# key_pad.net
KiCad netlist of a schematic drawn in Altium Designer
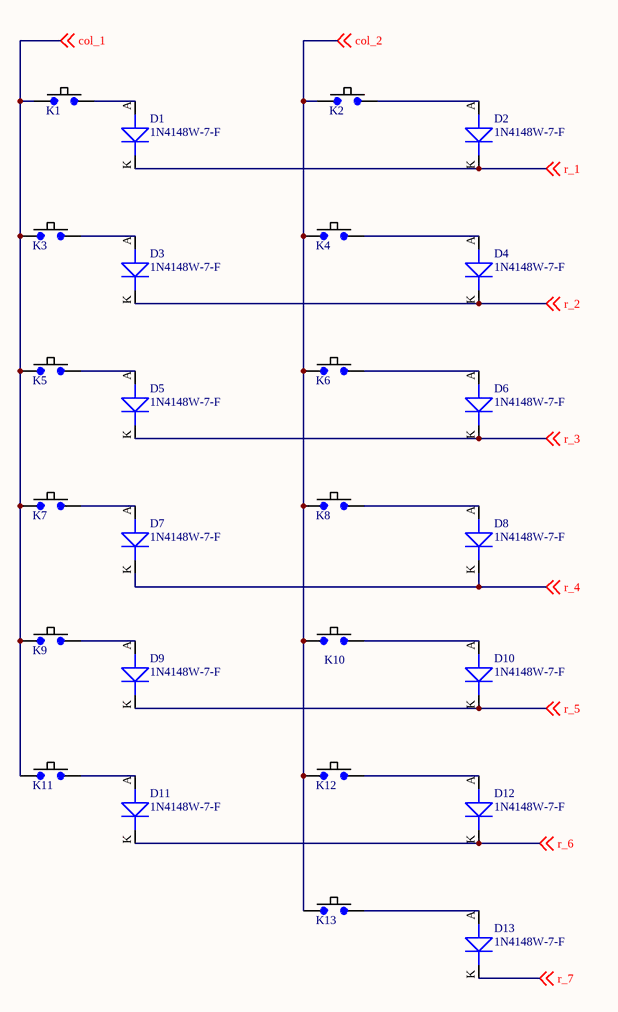
[diagram p0: key_pad.SchDoc]

(export (version "E")
  (design (tool "Eeschema 10.0.6"))
  (components
    (comp (ref "D1")
      (value "1N4148W-7-F")
      (footprint "DIO_SOD-123")
      (description "Diode Standard 100V 300mA (DC) Surface Mount SOD-123")
      (fields (field (name "MANUFACTURER") "FAIRCHILD"))
      (libsource (lib "ESTEEMPCBLIB") (part "DIO_100V-300mA-SOD123"))
    )
    (comp (ref "D2")
      (value "1N4148W-7-F")
      (footprint "DIO_SOD-123")
      (description "Diode Standard 100V 300mA (DC) Surface Mount SOD-123")
      (fields (field (name "MANUFACTURER") "FAIRCHILD"))
      (libsource (lib "ESTEEMPCBLIB") (part "DIO_100V-300mA-SOD123"))
    )
    (comp (ref "D3")
      (value "1N4148W-7-F")
      (footprint "DIO_SOD-123")
      (description "Diode Standard 100V 300mA (DC) Surface Mount SOD-123")
      (fields (field (name "MANUFACTURER") "FAIRCHILD"))
      (libsource (lib "ESTEEMPCBLIB") (part "DIO_100V-300mA-SOD123"))
    )
    (comp (ref "D4")
      (value "1N4148W-7-F")
      (footprint "DIO_SOD-123")
      (description "Diode Standard 100V 300mA (DC) Surface Mount SOD-123")
      (fields (field (name "MANUFACTURER") "FAIRCHILD"))
      (libsource (lib "ESTEEMPCBLIB") (part "DIO_100V-300mA-SOD123"))
    )
    (comp (ref "D5")
      (value "1N4148W-7-F")
      (footprint "DIO_SOD-123")
      (description "Diode Standard 100V 300mA (DC) Surface Mount SOD-123")
      (fields (field (name "MANUFACTURER") "FAIRCHILD"))
      (libsource (lib "ESTEEMPCBLIB") (part "DIO_100V-300mA-SOD123"))
    )
    (comp (ref "D6")
      (value "1N4148W-7-F")
      (footprint "DIO_SOD-123")
      (description "Diode Standard 100V 300mA (DC) Surface Mount SOD-123")
      (fields (field (name "MANUFACTURER") "FAIRCHILD"))
      (libsource (lib "ESTEEMPCBLIB") (part "DIO_100V-300mA-SOD123"))
    )
    (comp (ref "D7")
      (value "1N4148W-7-F")
      (footprint "DIO_SOD-123")
      (description "Diode Standard 100V 300mA (DC) Surface Mount SOD-123")
      (fields (field (name "MANUFACTURER") "FAIRCHILD"))
      (libsource (lib "ESTEEMPCBLIB") (part "DIO_100V-300mA-SOD123"))
    )
    (comp (ref "D8")
      (value "1N4148W-7-F")
      (footprint "DIO_SOD-123")
      (description "Diode Standard 100V 300mA (DC) Surface Mount SOD-123")
      (fields (field (name "MANUFACTURER") "FAIRCHILD"))
      (libsource (lib "ESTEEMPCBLIB") (part "DIO_100V-300mA-SOD123"))
    )
    (comp (ref "D9")
      (value "1N4148W-7-F")
      (footprint "DIO_SOD-123")
      (description "Diode Standard 100V 300mA (DC) Surface Mount SOD-123")
      (fields (field (name "MANUFACTURER") "FAIRCHILD"))
      (libsource (lib "ESTEEMPCBLIB") (part "DIO_100V-300mA-SOD123"))
    )
    (comp (ref "D10")
      (value "1N4148W-7-F")
      (footprint "DIO_SOD-123")
      (description "Diode Standard 100V 300mA (DC) Surface Mount SOD-123")
      (fields (field (name "MANUFACTURER") "FAIRCHILD"))
      (libsource (lib "ESTEEMPCBLIB") (part "DIO_100V-300mA-SOD123"))
    )
    (comp (ref "D11")
      (value "1N4148W-7-F")
      (footprint "DIO_SOD-123")
      (description "Diode Standard 100V 300mA (DC) Surface Mount SOD-123")
      (fields (field (name "MANUFACTURER") "FAIRCHILD"))
      (libsource (lib "ESTEEMPCBLIB") (part "DIO_100V-300mA-SOD123"))
    )
    (comp (ref "D12")
      (value "1N4148W-7-F")
      (footprint "DIO_SOD-123")
      (description "Diode Standard 100V 300mA (DC) Surface Mount SOD-123")
      (fields (field (name "MANUFACTURER") "FAIRCHILD"))
      (libsource (lib "ESTEEMPCBLIB") (part "DIO_100V-300mA-SOD123"))
    )
    (comp (ref "D13")
      (value "1N4148W-7-F")
      (footprint "DIO_SOD-123")
      (description "Diode Standard 100V 300mA (DC) Surface Mount SOD-123")
      (fields (field (name "MANUFACTURER") "FAIRCHILD"))
      (libsource (lib "ESTEEMPCBLIB") (part "DIO_100V-300mA-SOD123"))
    )
    (comp (ref "K1")
      (value "KEY PAD")
      (footprint "KEYPAD")
      (libsource (lib "walton1stmobile") (part "KEY PAD"))
    )
    (comp (ref "K2")
      (value "KEY PAD")
      (footprint "KEYPAD")
      (libsource (lib "walton1stmobile") (part "KEY PAD"))
    )
    (comp (ref "K3")
      (value "KEY PAD")
      (footprint "KEYPAD")
      (libsource (lib "walton1stmobile") (part "KEY PAD"))
    )
    (comp (ref "K4")
      (value "KEY PAD")
      (footprint "KEYPAD")
      (libsource (lib "walton1stmobile") (part "KEY PAD"))
    )
    (comp (ref "K5")
      (value "KEY PAD")
      (footprint "KEYPAD")
      (libsource (lib "walton1stmobile") (part "KEY PAD"))
    )
    (comp (ref "K6")
      (value "KEY PAD")
      (footprint "KEYPAD")
      (libsource (lib "walton1stmobile") (part "KEY PAD"))
    )
    (comp (ref "K7")
      (value "KEY PAD")
      (footprint "KEYPAD")
      (libsource (lib "walton1stmobile") (part "KEY PAD"))
    )
    (comp (ref "K8")
      (value "KEY PAD")
      (footprint "KEYPAD")
      (libsource (lib "walton1stmobile") (part "KEY PAD"))
    )
    (comp (ref "K9")
      (value "KEY PAD")
      (footprint "KEYPAD")
      (libsource (lib "walton1stmobile") (part "KEY PAD"))
    )
    (comp (ref "K10")
      (value "KEY PAD")
      (footprint "KEYPAD")
      (libsource (lib "walton1stmobile") (part "KEY PAD"))
    )
    (comp (ref "K11")
      (value "KEY PAD")
      (footprint "KEYPAD")
      (libsource (lib "walton1stmobile") (part "KEY PAD"))
    )
    (comp (ref "K12")
      (value "KEY PAD")
      (footprint "KEYPAD")
      (libsource (lib "walton1stmobile") (part "KEY PAD"))
    )
    (comp (ref "K13")
      (value "KEY PAD")
      (footprint "KEYPAD")
      (libsource (lib "walton1stmobile") (part "KEY PAD"))
    )
  )
  (nets
    (net (code "2") (name "Net-(D1-ANODE)") (class "Default")
      (node (ref "D1") (pin "A") (pinfunction "ANODE_A") (pintype "passive"))
      (node (ref "K1") (pin "2") (pintype "passive"))
    )
    (net (code "3") (name "Net-(D2-ANODE)") (class "Default")
      (node (ref "D2") (pin "A") (pinfunction "ANODE_A") (pintype "passive"))
      (node (ref "K2") (pin "2") (pintype "passive"))
    )
    (net (code "4") (name "Net-(D3-ANODE)") (class "Default")
      (node (ref "D3") (pin "A") (pinfunction "ANODE_A") (pintype "passive"))
      (node (ref "K3") (pin "2") (pintype "passive"))
    )
    (net (code "5") (name "Net-(D4-ANODE)") (class "Default")
      (node (ref "D4") (pin "A") (pinfunction "ANODE_A") (pintype "passive"))
      (node (ref "K4") (pin "2") (pintype "passive"))
    )
    (net (code "6") (name "Net-(D5-ANODE)") (class "Default")
      (node (ref "D5") (pin "A") (pinfunction "ANODE_A") (pintype "passive"))
      (node (ref "K5") (pin "2") (pintype "passive"))
    )
    (net (code "7") (name "Net-(D6-ANODE)") (class "Default")
      (node (ref "D6") (pin "A") (pinfunction "ANODE_A") (pintype "passive"))
      (node (ref "K6") (pin "2") (pintype "passive"))
    )
    (net (code "8") (name "Net-(D7-ANODE)") (class "Default")
      (node (ref "D7") (pin "A") (pinfunction "ANODE_A") (pintype "passive"))
      (node (ref "K7") (pin "2") (pintype "passive"))
    )
    (net (code "9") (name "Net-(D8-ANODE)") (class "Default")
      (node (ref "D8") (pin "A") (pinfunction "ANODE_A") (pintype "passive"))
      (node (ref "K8") (pin "2") (pintype "passive"))
    )
    (net (code "10") (name "Net-(D9-ANODE)") (class "Default")
      (node (ref "D9") (pin "A") (pinfunction "ANODE_A") (pintype "passive"))
      (node (ref "K9") (pin "2") (pintype "passive"))
    )
    (net (code "11") (name "Net-(D10-ANODE)") (class "Default")
      (node (ref "D10") (pin "A") (pinfunction "ANODE_A") (pintype "passive"))
      (node (ref "K10") (pin "2") (pintype "passive"))
    )
    (net (code "12") (name "Net-(D11-ANODE)") (class "Default")
      (node (ref "D11") (pin "A") (pinfunction "ANODE_A") (pintype "passive"))
      (node (ref "K11") (pin "2") (pintype "passive"))
    )
    (net (code "13") (name "Net-(D12-ANODE)") (class "Default")
      (node (ref "D12") (pin "A") (pinfunction "ANODE_A") (pintype "passive"))
      (node (ref "K12") (pin "2") (pintype "passive"))
    )
    (net (code "14") (name "Net-(D13-ANODE)") (class "Default")
      (node (ref "D13") (pin "A") (pinfunction "ANODE_A") (pintype "passive"))
      (node (ref "K13") (pin "2") (pintype "passive"))
    )
    (net (code "15") (name "col_1") (class "Default")
      (node (ref "K1") (pin "1") (pintype "passive"))
      (node (ref "K11") (pin "1") (pintype "passive"))
      (node (ref "K3") (pin "1") (pintype "passive"))
      (node (ref "K5") (pin "1") (pintype "passive"))
      (node (ref "K7") (pin "1") (pintype "passive"))
      (node (ref "K9") (pin "1") (pintype "passive"))
    )
    (net (code "16") (name "col_2") (class "Default")
      (node (ref "K10") (pin "1") (pintype "passive"))
      (node (ref "K12") (pin "1") (pintype "passive"))
      (node (ref "K13") (pin "1") (pintype "passive"))
      (node (ref "K2") (pin "1") (pintype "passive"))
      (node (ref "K4") (pin "1") (pintype "passive"))
      (node (ref "K6") (pin "1") (pintype "passive"))
      (node (ref "K8") (pin "1") (pintype "passive"))
    )
    (net (code "17") (name "r_1") (class "Default")
      (node (ref "D1") (pin "K") (pinfunction "CATHODE_K") (pintype "passive"))
      (node (ref "D2") (pin "K") (pinfunction "CATHODE_K") (pintype "passive"))
    )
    (net (code "18") (name "r_2") (class "Default")
      (node (ref "D3") (pin "K") (pinfunction "CATHODE_K") (pintype "passive"))
      (node (ref "D4") (pin "K") (pinfunction "CATHODE_K") (pintype "passive"))
    )
    (net (code "19") (name "r_3") (class "Default")
      (node (ref "D5") (pin "K") (pinfunction "CATHODE_K") (pintype "passive"))
      (node (ref "D6") (pin "K") (pinfunction "CATHODE_K") (pintype "passive"))
    )
    (net (code "20") (name "r_4") (class "Default")
      (node (ref "D7") (pin "K") (pinfunction "CATHODE_K") (pintype "passive"))
      (node (ref "D8") (pin "K") (pinfunction "CATHODE_K") (pintype "passive"))
    )
    (net (code "21") (name "r_5") (class "Default")
      (node (ref "D10") (pin "K") (pinfunction "CATHODE_K") (pintype "passive"))
      (node (ref "D9") (pin "K") (pinfunction "CATHODE_K") (pintype "passive"))
    )
    (net (code "22") (name "r_6") (class "Default")
      (node (ref "D11") (pin "K") (pinfunction "CATHODE_K") (pintype "passive"))
      (node (ref "D12") (pin "K") (pinfunction "CATHODE_K") (pintype "passive"))
    )
    (net (code "23") (name "r_7") (class "Default")
      (node (ref "D13") (pin "K") (pinfunction "CATHODE_K") (pintype "passive"))
    )
  )
)
